# RotaryEncoderBoard.net
KiCad netlist of a schematic drawn in EAGLE
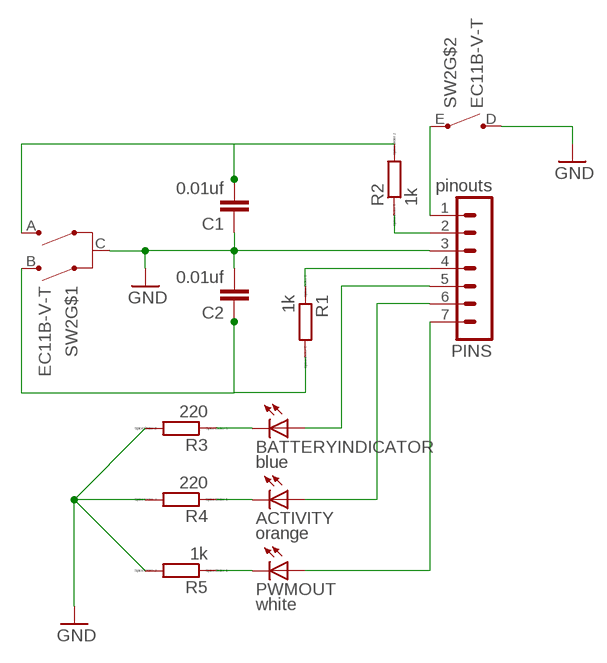
[diagram p0: schematic, sheet 1]

(export (version "E")
  (design (tool "Eeschema 10.0.6"))
  (components
    (comp (ref "ACTIVITY")
      (value "orange")
      (footprint "eagle-import:LED-1206")
      (libsource (lib "eagle-import") (part "LED1206"))
    )
    (comp (ref "BATTERYINDICATOR")
      (value "blue")
      (footprint "eagle-import:LED-1206")
      (libsource (lib "eagle-import") (part "LED1206"))
    )
    (comp (ref "C1")
      (value "0.01uf")
      (footprint "eagle-import:C2.5-3")
      (libsource (lib "eagle-import") (part "C2,5-3"))
    )
    (comp (ref "C2")
      (value "0.01uf")
      (footprint "eagle-import:C2.5-3")
      (libsource (lib "eagle-import") (part "C2,5-3"))
    )
    (comp (ref "PINS")
      (value "pinouts")
      (footprint "eagle-import:MA07-1")
      (libsource (lib "eagle-import") (part "MA07-1"))
    )
    (comp (ref "PWMOUT")
      (value "white")
      (footprint "eagle-import:LED-1206")
      (libsource (lib "eagle-import") (part "LED1206"))
    )
    (comp (ref "R1")
      (value "1k")
      (footprint "eagle-import:0204_7")
      (libsource (lib "eagle-import") (part "R0204/7"))
    )
    (comp (ref "R2")
      (value "1k")
      (footprint "eagle-import:0204_7")
      (libsource (lib "eagle-import") (part "R0204/7"))
    )
    (comp (ref "R3")
      (value "220")
      (footprint "eagle-import:0204_7")
      (libsource (lib "eagle-import") (part "R0204/7"))
    )
    (comp (ref "R4")
      (value "220")
      (footprint "eagle-import:0204_7")
      (libsource (lib "eagle-import") (part "R0204/7"))
    )
    (comp (ref "R5")
      (value "1k")
      (footprint "eagle-import:0204_7")
      (libsource (lib "eagle-import") (part "R0204/7"))
    )
    (comp (ref "SW2")
      (value "EC11B-V-T")
      (footprint "eagle-import:EC11B-V")
      (libsource (lib "eagle-import") (part "EC11B-V-T"))
    )
  )
  (nets
    (net (code "1") (name "GND") (class "Default")
      (node (ref "C1") (pin "1") (pinfunction "1_1") (pintype "passive"))
      (node (ref "C2") (pin "2") (pinfunction "2_2") (pintype "passive"))
      (node (ref "PINS") (pin "3") (pinfunction "3_3") (pintype "passive"))
      (node (ref "R3") (pin "2") (pinfunction "2_2") (pintype "passive"))
      (node (ref "R4") (pin "2") (pinfunction "2_2") (pintype "passive"))
      (node (ref "R5") (pin "2") (pinfunction "2_2") (pintype "passive"))
      (node (ref "SW2") (pin "C") (pinfunction "C_C") (pintype "passive"))
      (node (ref "SW2") (pin "D") (pinfunction "D_D") (pintype "passive"))
    )
    (net (code "2") (name "Net-(ACTIVITY-PadA)") (class "Default")
      (node (ref "ACTIVITY") (pin "A") (pinfunction "A_A") (pintype "passive"))
      (node (ref "PINS") (pin "6") (pinfunction "6_6") (pintype "passive"))
    )
    (net (code "3") (name "Net-(ACTIVITY-PadC)") (class "Default")
      (node (ref "ACTIVITY") (pin "C") (pinfunction "C_C") (pintype "passive"))
      (node (ref "R4") (pin "1") (pinfunction "1_1") (pintype "passive"))
    )
    (net (code "4") (name "Net-(BATTERYINDICATOR-PadA)") (class "Default")
      (node (ref "BATTERYINDICATOR") (pin "A") (pinfunction "A_A") (pintype "passive"))
      (node (ref "PINS") (pin "5") (pinfunction "5_5") (pintype "passive"))
    )
    (net (code "5") (name "Net-(BATTERYINDICATOR-PadC)") (class "Default")
      (node (ref "BATTERYINDICATOR") (pin "C") (pinfunction "C_C") (pintype "passive"))
      (node (ref "R3") (pin "1") (pinfunction "1_1") (pintype "passive"))
    )
    (net (code "6") (name "Net-(C1-Pad2)") (class "Default")
      (node (ref "C1") (pin "2") (pinfunction "2_2") (pintype "passive"))
      (node (ref "R2") (pin "2") (pinfunction "2_2") (pintype "passive"))
      (node (ref "SW2") (pin "A") (pinfunction "A_A") (pintype "passive"))
    )
    (net (code "7") (name "Net-(C2-Pad1)") (class "Default")
      (node (ref "C2") (pin "1") (pinfunction "1_1") (pintype "passive"))
      (node (ref "R1") (pin "2") (pinfunction "2_2") (pintype "passive"))
      (node (ref "SW2") (pin "B") (pinfunction "B_B") (pintype "passive"))
    )
    (net (code "8") (name "Net-(PINS-Pad1)") (class "Default")
      (node (ref "PINS") (pin "1") (pinfunction "1_1") (pintype "passive"))
      (node (ref "SW2") (pin "E") (pinfunction "E_E") (pintype "passive"))
    )
    (net (code "9") (name "Net-(PINS-Pad2)") (class "Default")
      (node (ref "PINS") (pin "2") (pinfunction "2_2") (pintype "passive"))
      (node (ref "R2") (pin "1") (pinfunction "1_1") (pintype "passive"))
    )
    (net (code "10") (name "Net-(PINS-Pad4)") (class "Default")
      (node (ref "PINS") (pin "4") (pinfunction "4_4") (pintype "passive"))
      (node (ref "R1") (pin "1") (pinfunction "1_1") (pintype "passive"))
    )
    (net (code "11") (name "Net-(PINS-Pad7)") (class "Default")
      (node (ref "PINS") (pin "7") (pinfunction "7_7") (pintype "passive"))
      (node (ref "PWMOUT") (pin "A") (pinfunction "A_A") (pintype "passive"))
    )
    (net (code "12") (name "Net-(PWMOUT-PadC)") (class "Default")
      (node (ref "PWMOUT") (pin "C") (pinfunction "C_C") (pintype "passive"))
      (node (ref "R5") (pin "1") (pinfunction "1_1") (pintype "passive"))
    )
  )
)
